# esp32-poe-thermocouple-hat.net
KiCad netlist of a schematic drawn in EAGLE
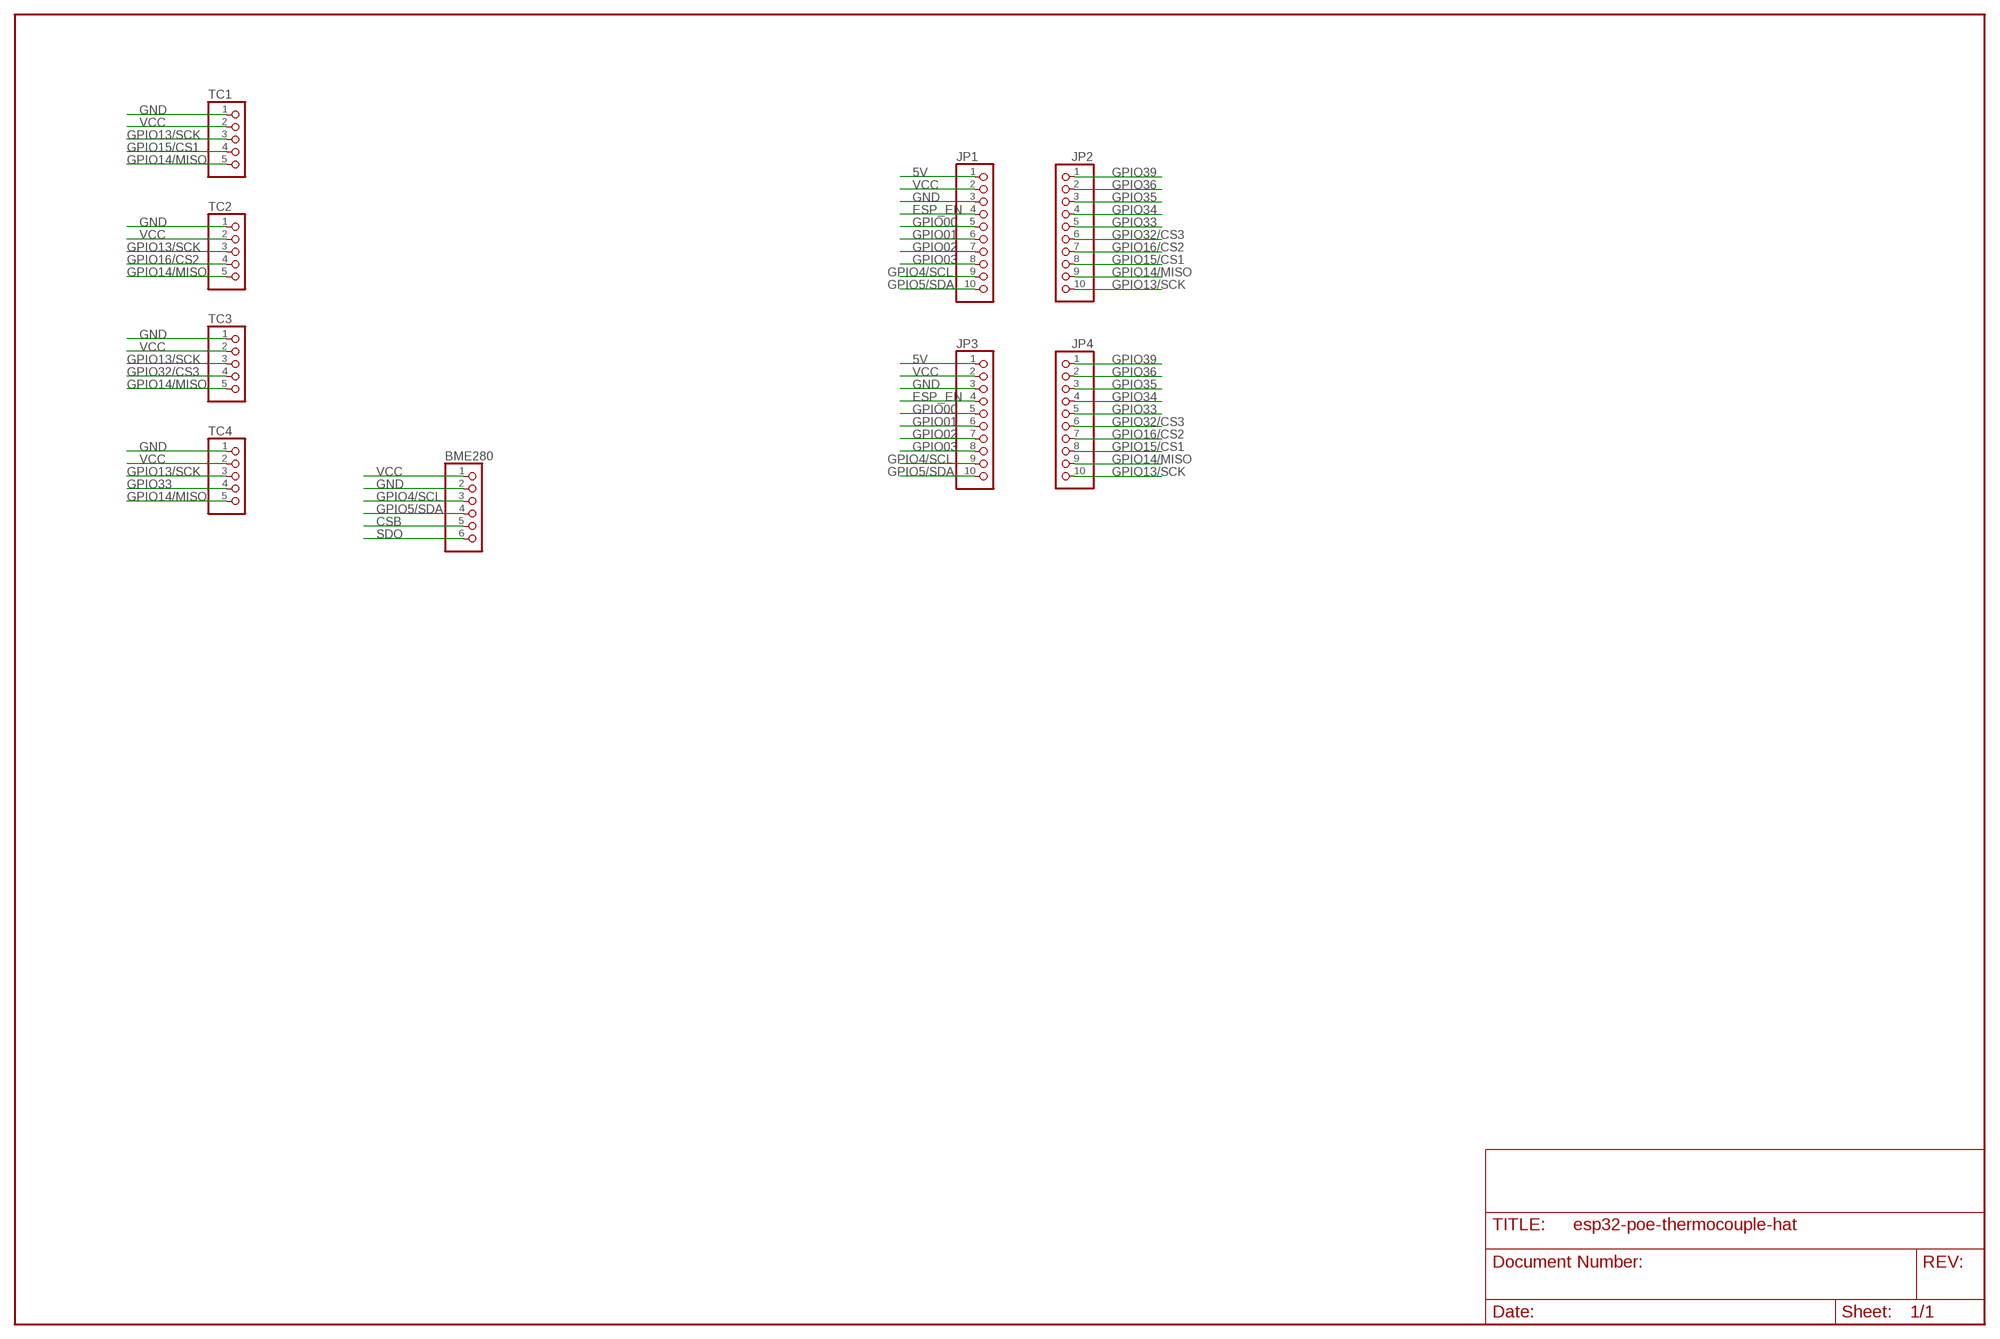
[diagram p0: schematic, sheet 1]

(export (version "E")
  (design (tool "Eeschema 10.0.6"))
  (components
    (comp (ref "BME280")
      (value "PINHD-1X6")
      (footprint "eagle-import:1X06")
      (libsource (lib "eagle-import") (part "PINHD-1X6"))
    )
    (comp (ref "JP1")
      (value "PINHD-1X10")
      (footprint "eagle-import:1X10")
      (libsource (lib "eagle-import") (part "PINHD-1X10"))
    )
    (comp (ref "JP2")
      (value "PINHD-1X10")
      (footprint "eagle-import:1X10")
      (libsource (lib "eagle-import") (part "PINHD-1X10"))
    )
    (comp (ref "JP3")
      (value "PINHD-1X10")
      (footprint "eagle-import:1X10")
      (libsource (lib "eagle-import") (part "PINHD-1X10"))
    )
    (comp (ref "JP4")
      (value "PINHD-1X10")
      (footprint "eagle-import:1X10")
      (libsource (lib "eagle-import") (part "PINHD-1X10"))
    )
    (comp (ref "TC1")
      (value "PINHD-1X5")
      (footprint "eagle-import:1X05")
      (libsource (lib "eagle-import") (part "PINHD-1X5"))
    )
    (comp (ref "TC2")
      (value "PINHD-1X5")
      (footprint "eagle-import:1X05")
      (libsource (lib "eagle-import") (part "PINHD-1X5"))
    )
    (comp (ref "TC3")
      (value "PINHD-1X5")
      (footprint "eagle-import:1X05")
      (libsource (lib "eagle-import") (part "PINHD-1X5"))
    )
    (comp (ref "TC4")
      (value "PINHD-1X5")
      (footprint "eagle-import:1X05")
      (libsource (lib "eagle-import") (part "PINHD-1X5"))
    )
  )
  (nets
    (net (code "1") (name "/5V") (class "Default")
      (node (ref "JP1") (pin "1") (pinfunction "1_1") (pintype "passive"))
      (node (ref "JP3") (pin "1") (pinfunction "1_1") (pintype "passive"))
    )
    (net (code "2") (name "/CSB") (class "Default")
      (node (ref "BME280") (pin "5") (pinfunction "5_5") (pintype "passive"))
    )
    (net (code "3") (name "/ESP_EN") (class "Default")
      (node (ref "JP1") (pin "4") (pinfunction "4_4") (pintype "passive"))
      (node (ref "JP3") (pin "4") (pinfunction "4_4") (pintype "passive"))
    )
    (net (code "4") (name "/GND") (class "Default")
      (node (ref "BME280") (pin "2") (pinfunction "2_2") (pintype "passive"))
      (node (ref "JP1") (pin "3") (pinfunction "3_3") (pintype "passive"))
      (node (ref "JP3") (pin "3") (pinfunction "3_3") (pintype "passive"))
      (node (ref "TC1") (pin "1") (pinfunction "1_1") (pintype "passive"))
      (node (ref "TC2") (pin "1") (pinfunction "1_1") (pintype "passive"))
      (node (ref "TC3") (pin "1") (pinfunction "1_1") (pintype "passive"))
      (node (ref "TC4") (pin "1") (pinfunction "1_1") (pintype "passive"))
    )
    (net (code "5") (name "/GPIO00") (class "Default")
      (node (ref "JP1") (pin "5") (pinfunction "5_5") (pintype "passive"))
      (node (ref "JP3") (pin "5") (pinfunction "5_5") (pintype "passive"))
    )
    (net (code "6") (name "/GPIO01") (class "Default")
      (node (ref "JP1") (pin "6") (pinfunction "6_6") (pintype "passive"))
      (node (ref "JP3") (pin "6") (pinfunction "6_6") (pintype "passive"))
    )
    (net (code "7") (name "/GPIO02") (class "Default")
      (node (ref "JP1") (pin "7") (pinfunction "7_7") (pintype "passive"))
      (node (ref "JP3") (pin "7") (pinfunction "7_7") (pintype "passive"))
    )
    (net (code "8") (name "/GPIO03") (class "Default")
      (node (ref "JP1") (pin "8") (pinfunction "8_8") (pintype "passive"))
      (node (ref "JP3") (pin "8") (pinfunction "8_8") (pintype "passive"))
    )
    (net (code "9") (name "/GPIO4{slash}SCL") (class "Default")
      (node (ref "BME280") (pin "3") (pinfunction "3_3") (pintype "passive"))
      (node (ref "JP1") (pin "9") (pinfunction "9_9") (pintype "passive"))
      (node (ref "JP3") (pin "9") (pinfunction "9_9") (pintype "passive"))
    )
    (net (code "10") (name "/GPIO5{slash}SDA") (class "Default")
      (node (ref "BME280") (pin "4") (pinfunction "4_4") (pintype "passive"))
      (node (ref "JP1") (pin "10") (pinfunction "10_10") (pintype "passive"))
      (node (ref "JP3") (pin "10") (pinfunction "10_10") (pintype "passive"))
    )
    (net (code "11") (name "/GPIO13{slash}SCK") (class "Default")
      (node (ref "JP2") (pin "10") (pinfunction "10_10") (pintype "passive"))
      (node (ref "JP4") (pin "10") (pinfunction "10_10") (pintype "passive"))
      (node (ref "TC1") (pin "3") (pinfunction "3_3") (pintype "passive"))
      (node (ref "TC2") (pin "3") (pinfunction "3_3") (pintype "passive"))
      (node (ref "TC3") (pin "3") (pinfunction "3_3") (pintype "passive"))
      (node (ref "TC4") (pin "3") (pinfunction "3_3") (pintype "passive"))
    )
    (net (code "12") (name "/GPIO14{slash}MISO") (class "Default")
      (node (ref "JP2") (pin "9") (pinfunction "9_9") (pintype "passive"))
      (node (ref "JP4") (pin "9") (pinfunction "9_9") (pintype "passive"))
      (node (ref "TC1") (pin "5") (pinfunction "5_5") (pintype "passive"))
      (node (ref "TC2") (pin "5") (pinfunction "5_5") (pintype "passive"))
      (node (ref "TC3") (pin "5") (pinfunction "5_5") (pintype "passive"))
      (node (ref "TC4") (pin "5") (pinfunction "5_5") (pintype "passive"))
    )
    (net (code "13") (name "/GPIO15{slash}CS1") (class "Default")
      (node (ref "JP2") (pin "8") (pinfunction "8_8") (pintype "passive"))
      (node (ref "JP4") (pin "8") (pinfunction "8_8") (pintype "passive"))
      (node (ref "TC1") (pin "4") (pinfunction "4_4") (pintype "passive"))
    )
    (net (code "14") (name "/GPIO16{slash}CS2") (class "Default")
      (node (ref "JP2") (pin "7") (pinfunction "7_7") (pintype "passive"))
      (node (ref "JP4") (pin "7") (pinfunction "7_7") (pintype "passive"))
      (node (ref "TC2") (pin "4") (pinfunction "4_4") (pintype "passive"))
    )
    (net (code "15") (name "/GPIO32{slash}CS3") (class "Default")
      (node (ref "JP2") (pin "6") (pinfunction "6_6") (pintype "passive"))
      (node (ref "JP4") (pin "6") (pinfunction "6_6") (pintype "passive"))
      (node (ref "TC3") (pin "4") (pinfunction "4_4") (pintype "passive"))
    )
    (net (code "16") (name "/GPIO33") (class "Default")
      (node (ref "JP2") (pin "5") (pinfunction "5_5") (pintype "passive"))
      (node (ref "JP4") (pin "5") (pinfunction "5_5") (pintype "passive"))
      (node (ref "TC4") (pin "4") (pinfunction "4_4") (pintype "passive"))
    )
    (net (code "17") (name "/GPIO34") (class "Default")
      (node (ref "JP2") (pin "4") (pinfunction "4_4") (pintype "passive"))
      (node (ref "JP4") (pin "4") (pinfunction "4_4") (pintype "passive"))
    )
    (net (code "18") (name "/GPIO35") (class "Default")
      (node (ref "JP2") (pin "3") (pinfunction "3_3") (pintype "passive"))
      (node (ref "JP4") (pin "3") (pinfunction "3_3") (pintype "passive"))
    )
    (net (code "19") (name "/GPIO36") (class "Default")
      (node (ref "JP2") (pin "2") (pinfunction "2_2") (pintype "passive"))
      (node (ref "JP4") (pin "2") (pinfunction "2_2") (pintype "passive"))
    )
    (net (code "20") (name "/GPIO39") (class "Default")
      (node (ref "JP2") (pin "1") (pinfunction "1_1") (pintype "passive"))
      (node (ref "JP4") (pin "1") (pinfunction "1_1") (pintype "passive"))
    )
    (net (code "21") (name "/SDO") (class "Default")
      (node (ref "BME280") (pin "6") (pinfunction "6_6") (pintype "passive"))
    )
    (net (code "22") (name "/VCC") (class "Default")
      (node (ref "BME280") (pin "1") (pinfunction "1_1") (pintype "passive"))
      (node (ref "JP1") (pin "2") (pinfunction "2_2") (pintype "passive"))
      (node (ref "JP3") (pin "2") (pinfunction "2_2") (pintype "passive"))
      (node (ref "TC1") (pin "2") (pinfunction "2_2") (pintype "passive"))
      (node (ref "TC2") (pin "2") (pinfunction "2_2") (pintype "passive"))
      (node (ref "TC3") (pin "2") (pinfunction "2_2") (pintype "passive"))
      (node (ref "TC4") (pin "2") (pinfunction "2_2") (pintype "passive"))
    )
  )
)
